# osh_fab_tolerance_test.net
KiCad netlist of a schematic drawn in EAGLE
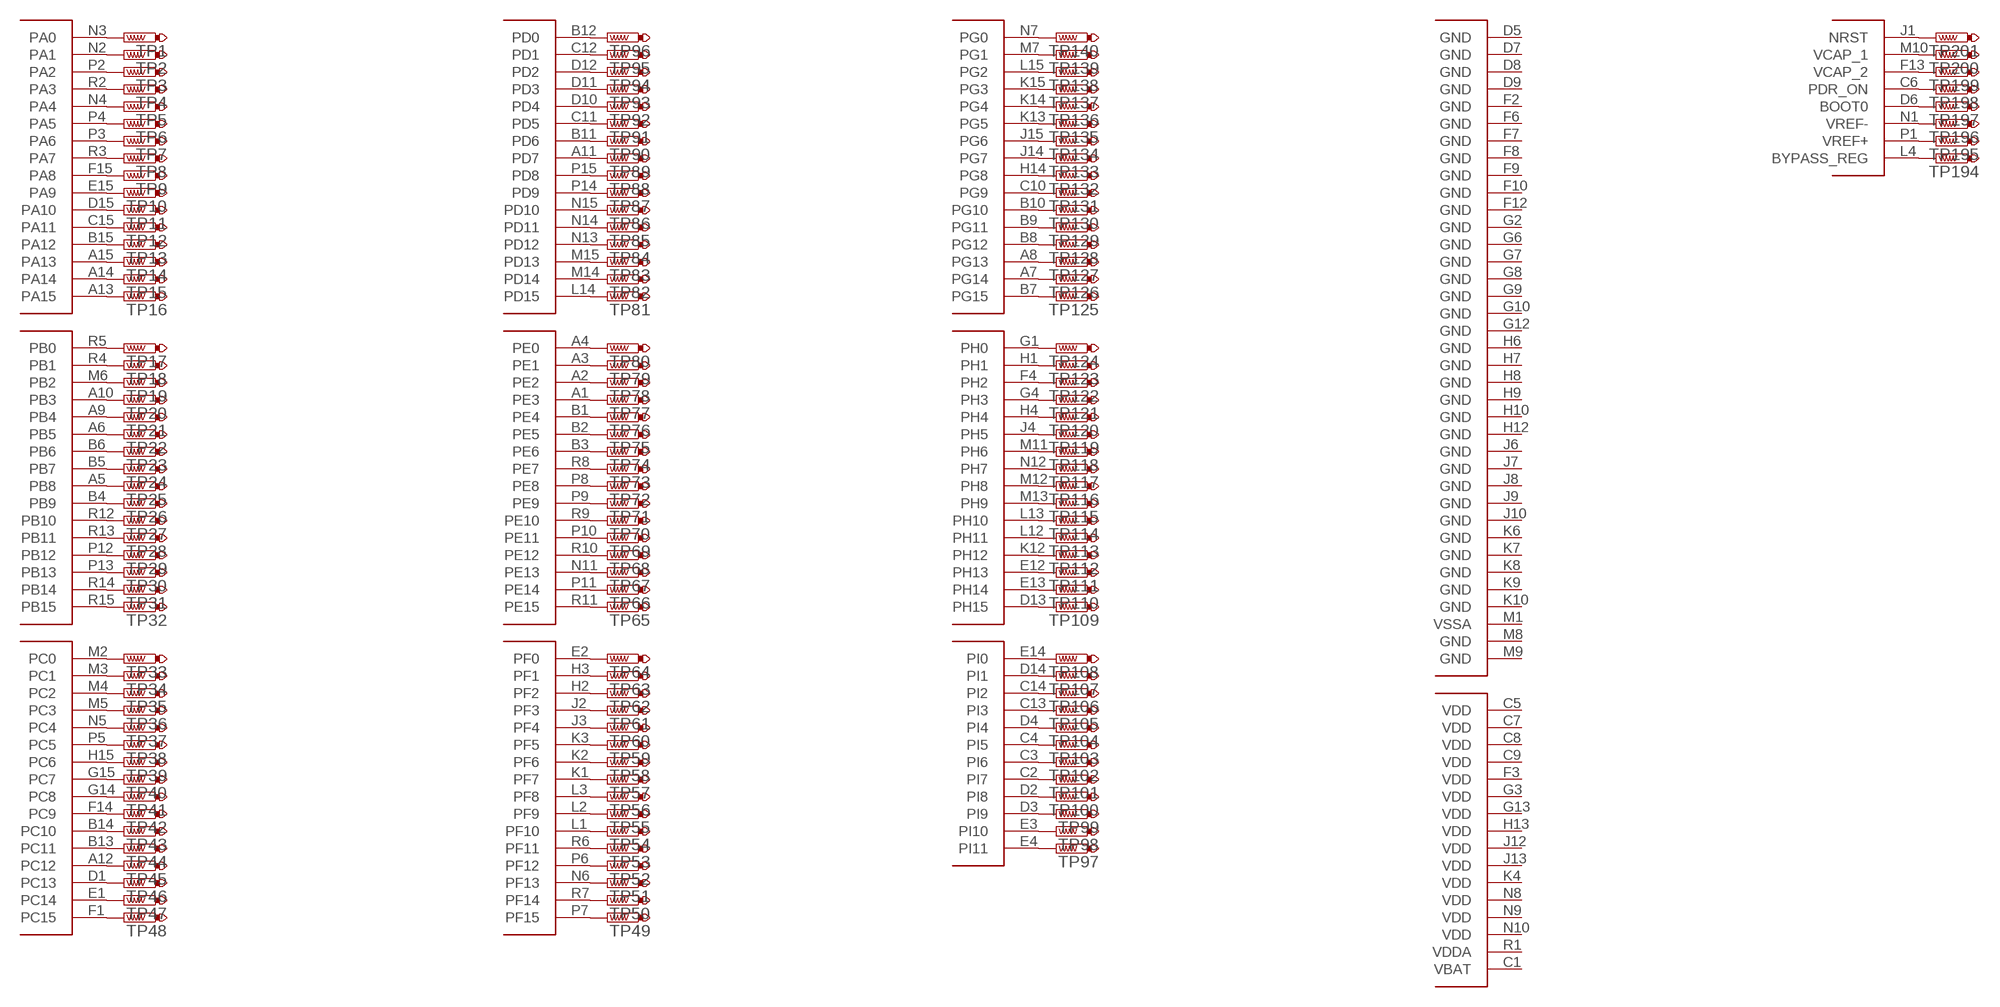
[diagram p0: schematic, sheet 1]

(export (version "E")
  (design (tool "Eeschema 10.0.6"))
  (components
    (comp (ref "TP1")
      (value "PTR1TP09R")
      (footprint "eagle-import:TP09R")
      (libsource (lib "eagle-import") (part "PTR1TP09R"))
    )
    (comp (ref "TP2")
      (value "PTR1TP09R")
      (footprint "eagle-import:TP09R")
      (libsource (lib "eagle-import") (part "PTR1TP09R"))
    )
    (comp (ref "TP3")
      (value "PTR1TP09R")
      (footprint "eagle-import:TP09R")
      (libsource (lib "eagle-import") (part "PTR1TP09R"))
    )
    (comp (ref "TP4")
      (value "PTR1TP09R")
      (footprint "eagle-import:TP09R")
      (libsource (lib "eagle-import") (part "PTR1TP09R"))
    )
    (comp (ref "TP5")
      (value "PTR1TP09R")
      (footprint "eagle-import:TP09R")
      (libsource (lib "eagle-import") (part "PTR1TP09R"))
    )
    (comp (ref "TP6")
      (value "PTR1TP09R")
      (footprint "eagle-import:TP09R")
      (libsource (lib "eagle-import") (part "PTR1TP09R"))
    )
    (comp (ref "TP7")
      (value "PTR1TP09R")
      (footprint "eagle-import:TP09R")
      (libsource (lib "eagle-import") (part "PTR1TP09R"))
    )
    (comp (ref "TP8")
      (value "PTR1TP09R")
      (footprint "eagle-import:TP09R")
      (libsource (lib "eagle-import") (part "PTR1TP09R"))
    )
    (comp (ref "TP9")
      (value "PTR1TP09R")
      (footprint "eagle-import:TP09R")
      (libsource (lib "eagle-import") (part "PTR1TP09R"))
    )
    (comp (ref "TP10")
      (value "PTR1TP09R")
      (footprint "eagle-import:TP09R")
      (libsource (lib "eagle-import") (part "PTR1TP09R"))
    )
    (comp (ref "TP11")
      (value "PTR1TP09R")
      (footprint "eagle-import:TP09R")
      (libsource (lib "eagle-import") (part "PTR1TP09R"))
    )
    (comp (ref "TP12")
      (value "PTR1TP09R")
      (footprint "eagle-import:TP09R")
      (libsource (lib "eagle-import") (part "PTR1TP09R"))
    )
    (comp (ref "TP13")
      (value "PTR1TP09R")
      (footprint "eagle-import:TP09R")
      (libsource (lib "eagle-import") (part "PTR1TP09R"))
    )
    (comp (ref "TP14")
      (value "PTR1TP09R")
      (footprint "eagle-import:TP09R")
      (libsource (lib "eagle-import") (part "PTR1TP09R"))
    )
    (comp (ref "TP15")
      (value "PTR1TP09R")
      (footprint "eagle-import:TP09R")
      (libsource (lib "eagle-import") (part "PTR1TP09R"))
    )
    (comp (ref "TP16")
      (value "PTR1TP09R")
      (footprint "eagle-import:TP09R")
      (libsource (lib "eagle-import") (part "PTR1TP09R"))
    )
    (comp (ref "TP17")
      (value "PTR1TP09R")
      (footprint "eagle-import:TP09R")
      (libsource (lib "eagle-import") (part "PTR1TP09R"))
    )
    (comp (ref "TP18")
      (value "PTR1TP09R")
      (footprint "eagle-import:TP09R")
      (libsource (lib "eagle-import") (part "PTR1TP09R"))
    )
    (comp (ref "TP19")
      (value "PTR1TP09R")
      (footprint "eagle-import:TP09R")
      (libsource (lib "eagle-import") (part "PTR1TP09R"))
    )
    (comp (ref "TP20")
      (value "PTR1TP09R")
      (footprint "eagle-import:TP09R")
      (libsource (lib "eagle-import") (part "PTR1TP09R"))
    )
    (comp (ref "TP21")
      (value "PTR1TP09R")
      (footprint "eagle-import:TP09R")
      (libsource (lib "eagle-import") (part "PTR1TP09R"))
    )
    (comp (ref "TP22")
      (value "PTR1TP09R")
      (footprint "eagle-import:TP09R")
      (libsource (lib "eagle-import") (part "PTR1TP09R"))
    )
    (comp (ref "TP23")
      (value "PTR1TP09R")
      (footprint "eagle-import:TP09R")
      (libsource (lib "eagle-import") (part "PTR1TP09R"))
    )
    (comp (ref "TP24")
      (value "PTR1TP09R")
      (footprint "eagle-import:TP09R")
      (libsource (lib "eagle-import") (part "PTR1TP09R"))
    )
    (comp (ref "TP25")
      (value "PTR1TP09R")
      (footprint "eagle-import:TP09R")
      (libsource (lib "eagle-import") (part "PTR1TP09R"))
    )
    (comp (ref "TP26")
      (value "PTR1TP09R")
      (footprint "eagle-import:TP09R")
      (libsource (lib "eagle-import") (part "PTR1TP09R"))
    )
    (comp (ref "TP27")
      (value "PTR1TP09R")
      (footprint "eagle-import:TP09R")
      (libsource (lib "eagle-import") (part "PTR1TP09R"))
    )
    (comp (ref "TP28")
      (value "PTR1TP09R")
      (footprint "eagle-import:TP09R")
      (libsource (lib "eagle-import") (part "PTR1TP09R"))
    )
    (comp (ref "TP29")
      (value "PTR1TP09R")
      (footprint "eagle-import:TP09R")
      (libsource (lib "eagle-import") (part "PTR1TP09R"))
    )
    (comp (ref "TP30")
      (value "PTR1TP09R")
      (footprint "eagle-import:TP09R")
      (libsource (lib "eagle-import") (part "PTR1TP09R"))
    )
    (comp (ref "TP31")
      (value "PTR1TP09R")
      (footprint "eagle-import:TP09R")
      (libsource (lib "eagle-import") (part "PTR1TP09R"))
    )
    (comp (ref "TP32")
      (value "PTR1TP09R")
      (footprint "eagle-import:TP09R")
      (libsource (lib "eagle-import") (part "PTR1TP09R"))
    )
    (comp (ref "TP33")
      (value "PTR1TP09R")
      (footprint "eagle-import:TP09R")
      (libsource (lib "eagle-import") (part "PTR1TP09R"))
    )
    (comp (ref "TP34")
      (value "PTR1TP09R")
      (footprint "eagle-import:TP09R")
      (libsource (lib "eagle-import") (part "PTR1TP09R"))
    )
    (comp (ref "TP35")
      (value "PTR1TP09R")
      (footprint "eagle-import:TP09R")
      (libsource (lib "eagle-import") (part "PTR1TP09R"))
    )
    (comp (ref "TP36")
      (value "PTR1TP09R")
      (footprint "eagle-import:TP09R")
      (libsource (lib "eagle-import") (part "PTR1TP09R"))
    )
    (comp (ref "TP37")
      (value "PTR1TP09R")
      (footprint "eagle-import:TP09R")
      (libsource (lib "eagle-import") (part "PTR1TP09R"))
    )
    (comp (ref "TP38")
      (value "PTR1TP09R")
      (footprint "eagle-import:TP09R")
      (libsource (lib "eagle-import") (part "PTR1TP09R"))
    )
    (comp (ref "TP39")
      (value "PTR1TP09R")
      (footprint "eagle-import:TP09R")
      (libsource (lib "eagle-import") (part "PTR1TP09R"))
    )
    (comp (ref "TP40")
      (value "PTR1TP09R")
      (footprint "eagle-import:TP09R")
      (libsource (lib "eagle-import") (part "PTR1TP09R"))
    )
    (comp (ref "TP41")
      (value "PTR1TP09R")
      (footprint "eagle-import:TP09R")
      (libsource (lib "eagle-import") (part "PTR1TP09R"))
    )
    (comp (ref "TP42")
      (value "PTR1TP09R")
      (footprint "eagle-import:TP09R")
      (libsource (lib "eagle-import") (part "PTR1TP09R"))
    )
    (comp (ref "TP43")
      (value "PTR1TP09R")
      (footprint "eagle-import:TP09R")
      (libsource (lib "eagle-import") (part "PTR1TP09R"))
    )
    (comp (ref "TP44")
      (value "PTR1TP09R")
      (footprint "eagle-import:TP09R")
      (libsource (lib "eagle-import") (part "PTR1TP09R"))
    )
    (comp (ref "TP45")
      (value "PTR1TP09R")
      (footprint "eagle-import:TP09R")
      (libsource (lib "eagle-import") (part "PTR1TP09R"))
    )
    (comp (ref "TP46")
      (value "PTR1TP09R")
      (footprint "eagle-import:TP09R")
      (libsource (lib "eagle-import") (part "PTR1TP09R"))
    )
    (comp (ref "TP47")
      (value "PTR1TP09R")
      (footprint "eagle-import:TP09R")
      (libsource (lib "eagle-import") (part "PTR1TP09R"))
    )
    (comp (ref "TP48")
      (value "PTR1TP09R")
      (footprint "eagle-import:TP09R")
      (libsource (lib "eagle-import") (part "PTR1TP09R"))
    )
    (comp (ref "TP49")
      (value "PTR1TP09R")
      (footprint "eagle-import:TP09R")
      (libsource (lib "eagle-import") (part "PTR1TP09R"))
    )
    (comp (ref "TP50")
      (value "PTR1TP09R")
      (footprint "eagle-import:TP09R")
      (libsource (lib "eagle-import") (part "PTR1TP09R"))
    )
    (comp (ref "TP51")
      (value "PTR1TP09R")
      (footprint "eagle-import:TP09R")
      (libsource (lib "eagle-import") (part "PTR1TP09R"))
    )
    (comp (ref "TP52")
      (value "PTR1TP09R")
      (footprint "eagle-import:TP09R")
      (libsource (lib "eagle-import") (part "PTR1TP09R"))
    )
    (comp (ref "TP53")
      (value "PTR1TP09R")
      (footprint "eagle-import:TP09R")
      (libsource (lib "eagle-import") (part "PTR1TP09R"))
    )
    (comp (ref "TP54")
      (value "PTR1TP09R")
      (footprint "eagle-import:TP09R")
      (libsource (lib "eagle-import") (part "PTR1TP09R"))
    )
    (comp (ref "TP55")
      (value "PTR1TP09R")
      (footprint "eagle-import:TP09R")
      (libsource (lib "eagle-import") (part "PTR1TP09R"))
    )
    (comp (ref "TP56")
      (value "PTR1TP09R")
      (footprint "eagle-import:TP09R")
      (libsource (lib "eagle-import") (part "PTR1TP09R"))
    )
    (comp (ref "TP57")
      (value "PTR1TP09R")
      (footprint "eagle-import:TP09R")
      (libsource (lib "eagle-import") (part "PTR1TP09R"))
    )
    (comp (ref "TP58")
      (value "PTR1TP09R")
      (footprint "eagle-import:TP09R")
      (libsource (lib "eagle-import") (part "PTR1TP09R"))
    )
    (comp (ref "TP59")
      (value "PTR1TP09R")
      (footprint "eagle-import:TP09R")
      (libsource (lib "eagle-import") (part "PTR1TP09R"))
    )
    (comp (ref "TP60")
      (value "PTR1TP09R")
      (footprint "eagle-import:TP09R")
      (libsource (lib "eagle-import") (part "PTR1TP09R"))
    )
    (comp (ref "TP61")
      (value "PTR1TP09R")
      (footprint "eagle-import:TP09R")
      (libsource (lib "eagle-import") (part "PTR1TP09R"))
    )
    (comp (ref "TP62")
      (value "PTR1TP09R")
      (footprint "eagle-import:TP09R")
      (libsource (lib "eagle-import") (part "PTR1TP09R"))
    )
    (comp (ref "TP63")
      (value "PTR1TP09R")
      (footprint "eagle-import:TP09R")
      (libsource (lib "eagle-import") (part "PTR1TP09R"))
    )
    (comp (ref "TP64")
      (value "PTR1TP09R")
      (footprint "eagle-import:TP09R")
      (libsource (lib "eagle-import") (part "PTR1TP09R"))
    )
    (comp (ref "TP65")
      (value "PTR1TP09R")
      (footprint "eagle-import:TP09R")
      (libsource (lib "eagle-import") (part "PTR1TP09R"))
    )
    (comp (ref "TP66")
      (value "PTR1TP09R")
      (footprint "eagle-import:TP09R")
      (libsource (lib "eagle-import") (part "PTR1TP09R"))
    )
    (comp (ref "TP67")
      (value "PTR1TP09R")
      (footprint "eagle-import:TP09R")
      (libsource (lib "eagle-import") (part "PTR1TP09R"))
    )
    (comp (ref "TP68")
      (value "PTR1TP09R")
      (footprint "eagle-import:TP09R")
      (libsource (lib "eagle-import") (part "PTR1TP09R"))
    )
    (comp (ref "TP69")
      (value "PTR1TP09R")
      (footprint "eagle-import:TP09R")
      (libsource (lib "eagle-import") (part "PTR1TP09R"))
    )
    (comp (ref "TP70")
      (value "PTR1TP09R")
      (footprint "eagle-import:TP09R")
      (libsource (lib "eagle-import") (part "PTR1TP09R"))
    )
    (comp (ref "TP71")
      (value "PTR1TP09R")
      (footprint "eagle-import:TP09R")
      (libsource (lib "eagle-import") (part "PTR1TP09R"))
    )
    (comp (ref "TP72")
      (value "PTR1TP09R")
      (footprint "eagle-import:TP09R")
      (libsource (lib "eagle-import") (part "PTR1TP09R"))
    )
    (comp (ref "TP73")
      (value "PTR1TP09R")
      (footprint "eagle-import:TP09R")
      (libsource (lib "eagle-import") (part "PTR1TP09R"))
    )
    (comp (ref "TP74")
      (value "PTR1TP09R")
      (footprint "eagle-import:TP09R")
      (libsource (lib "eagle-import") (part "PTR1TP09R"))
    )
    (comp (ref "TP75")
      (value "PTR1TP09R")
      (footprint "eagle-import:TP09R")
      (libsource (lib "eagle-import") (part "PTR1TP09R"))
    )
    (comp (ref "TP76")
      (value "PTR1TP09R")
      (footprint "eagle-import:TP09R")
      (libsource (lib "eagle-import") (part "PTR1TP09R"))
    )
    (comp (ref "TP77")
      (value "PTR1TP09R")
      (footprint "eagle-import:TP09R")
      (libsource (lib "eagle-import") (part "PTR1TP09R"))
    )
    (comp (ref "TP78")
      (value "PTR1TP09R")
      (footprint "eagle-import:TP09R")
      (libsource (lib "eagle-import") (part "PTR1TP09R"))
    )
    (comp (ref "TP79")
      (value "PTR1TP09R")
      (footprint "eagle-import:TP09R")
      (libsource (lib "eagle-import") (part "PTR1TP09R"))
    )
    (comp (ref "TP80")
      (value "PTR1TP09R")
      (footprint "eagle-import:TP09R")
      (libsource (lib "eagle-import") (part "PTR1TP09R"))
    )
    (comp (ref "TP81")
      (value "PTR1TP09R")
      (footprint "eagle-import:TP09R")
      (libsource (lib "eagle-import") (part "PTR1TP09R"))
    )
    (comp (ref "TP82")
      (value "PTR1TP09R")
      (footprint "eagle-import:TP09R")
      (libsource (lib "eagle-import") (part "PTR1TP09R"))
    )
    (comp (ref "TP83")
      (value "PTR1TP09R")
      (footprint "eagle-import:TP09R")
      (libsource (lib "eagle-import") (part "PTR1TP09R"))
    )
    (comp (ref "TP84")
      (value "PTR1TP09R")
      (footprint "eagle-import:TP09R")
      (libsource (lib "eagle-import") (part "PTR1TP09R"))
    )
    (comp (ref "TP85")
      (value "PTR1TP09R")
      (footprint "eagle-import:TP09R")
      (libsource (lib "eagle-import") (part "PTR1TP09R"))
    )
    (comp (ref "TP86")
      (value "PTR1TP09R")
      (footprint "eagle-import:TP09R")
      (libsource (lib "eagle-import") (part "PTR1TP09R"))
    )
    (comp (ref "TP87")
      (value "PTR1TP09R")
      (footprint "eagle-import:TP09R")
      (libsource (lib "eagle-import") (part "PTR1TP09R"))
    )
    (comp (ref "TP88")
      (value "PTR1TP09R")
      (footprint "eagle-import:TP09R")
      (libsource (lib "eagle-import") (part "PTR1TP09R"))
    )
    (comp (ref "TP89")
      (value "PTR1TP09R")
      (footprint "eagle-import:TP09R")
      (libsource (lib "eagle-import") (part "PTR1TP09R"))
    )
    (comp (ref "TP90")
      (value "PTR1TP09R")
      (footprint "eagle-import:TP09R")
      (libsource (lib "eagle-import") (part "PTR1TP09R"))
    )
    (comp (ref "TP91")
      (value "PTR1TP09R")
      (footprint "eagle-import:TP09R")
      (libsource (lib "eagle-import") (part "PTR1TP09R"))
    )
    (comp (ref "TP92")
      (value "PTR1TP09R")
      (footprint "eagle-import:TP09R")
      (libsource (lib "eagle-import") (part "PTR1TP09R"))
    )
    (comp (ref "TP93")
      (value "PTR1TP09R")
      (footprint "eagle-import:TP09R")
      (libsource (lib "eagle-import") (part "PTR1TP09R"))
    )
    (comp (ref "TP94")
      (value "PTR1TP09R")
      (footprint "eagle-import:TP09R")
      (libsource (lib "eagle-import") (part "PTR1TP09R"))
    )
    (comp (ref "TP95")
      (value "PTR1TP09R")
      (footprint "eagle-import:TP09R")
      (libsource (lib "eagle-import") (part "PTR1TP09R"))
    )
    (comp (ref "TP96")
      (value "PTR1TP09R")
      (footprint "eagle-import:TP09R")
      (libsource (lib "eagle-import") (part "PTR1TP09R"))
    )
    (comp (ref "TP97")
      (value "PTR1TP09R")
      (footprint "eagle-import:TP09R")
      (libsource (lib "eagle-import") (part "PTR1TP09R"))
    )
    (comp (ref "TP98")
      (value "PTR1TP09R")
      (footprint "eagle-import:TP09R")
      (libsource (lib "eagle-import") (part "PTR1TP09R"))
    )
    (comp (ref "TP99")
      (value "PTR1TP09R")
      (footprint "eagle-import:TP09R")
      (libsource (lib "eagle-import") (part "PTR1TP09R"))
    )
    (comp (ref "TP100")
      (value "PTR1TP09R")
      (footprint "eagle-import:TP09R")
      (libsource (lib "eagle-import") (part "PTR1TP09R"))
    )
    (comp (ref "TP101")
      (value "PTR1TP09R")
      (footprint "eagle-import:TP09R")
      (libsource (lib "eagle-import") (part "PTR1TP09R"))
    )
    (comp (ref "TP102")
      (value "PTR1TP09R")
      (footprint "eagle-import:TP09R")
      (libsource (lib "eagle-import") (part "PTR1TP09R"))
    )
    (comp (ref "TP103")
      (value "PTR1TP09R")
      (footprint "eagle-import:TP09R")
      (libsource (lib "eagle-import") (part "PTR1TP09R"))
    )
    (comp (ref "TP104")
      (value "PTR1TP09R")
      (footprint "eagle-import:TP09R")
      (libsource (lib "eagle-import") (part "PTR1TP09R"))
    )
    (comp (ref "TP105")
      (value "PTR1TP09R")
      (footprint "eagle-import:TP09R")
      (libsource (lib "eagle-import") (part "PTR1TP09R"))
    )
    (comp (ref "TP106")
      (value "PTR1TP09R")
      (footprint "eagle-import:TP09R")
      (libsource (lib "eagle-import") (part "PTR1TP09R"))
    )
    (comp (ref "TP107")
      (value "PTR1TP09R")
      (footprint "eagle-import:TP09R")
      (libsource (lib "eagle-import") (part "PTR1TP09R"))
    )
    (comp (ref "TP108")
      (value "PTR1TP09R")
      (footprint "eagle-import:TP09R")
      (libsource (lib "eagle-import") (part "PTR1TP09R"))
    )
    (comp (ref "TP109")
      (value "PTR1TP09R")
      (footprint "eagle-import:TP09R")
      (libsource (lib "eagle-import") (part "PTR1TP09R"))
    )
    (comp (ref "TP110")
      (value "PTR1TP09R")
      (footprint "eagle-import:TP09R")
      (libsource (lib "eagle-import") (part "PTR1TP09R"))
    )
    (comp (ref "TP111")
      (value "PTR1TP09R")
      (footprint "eagle-import:TP09R")
      (libsource (lib "eagle-import") (part "PTR1TP09R"))
    )
    (comp (ref "TP112")
      (value "PTR1TP09R")
      (footprint "eagle-import:TP09R")
      (libsource (lib "eagle-import") (part "PTR1TP09R"))
    )
    (comp (ref "TP113")
      (value "PTR1TP09R")
      (footprint "eagle-import:TP09R")
      (libsource (lib "eagle-import") (part "PTR1TP09R"))
    )
    (comp (ref "TP114")
      (value "PTR1TP09R")
      (footprint "eagle-import:TP09R")
      (libsource (lib "eagle-import") (part "PTR1TP09R"))
    )
    (comp (ref "TP115")
      (value "PTR1TP09R")
      (footprint "eagle-import:TP09R")
      (libsource (lib "eagle-import") (part "PTR1TP09R"))
    )
    (comp (ref "TP116")
      (value "PTR1TP09R")
      (footprint "eagle-import:TP09R")
      (libsource (lib "eagle-import") (part "PTR1TP09R"))
    )
    (comp (ref "TP117")
      (value "PTR1TP09R")
      (footprint "eagle-import:TP09R")
      (libsource (lib "eagle-import") (part "PTR1TP09R"))
    )
    (comp (ref "TP118")
      (value "PTR1TP09R")
      (footprint "eagle-import:TP09R")
      (libsource (lib "eagle-import") (part "PTR1TP09R"))
    )
    (comp (ref "TP119")
      (value "PTR1TP09R")
      (footprint "eagle-import:TP09R")
      (libsource (lib "eagle-import") (part "PTR1TP09R"))
    )
    (comp (ref "TP120")
      (value "PTR1TP09R")
      (footprint "eagle-import:TP09R")
      (libsource (lib "eagle-import") (part "PTR1TP09R"))
    )
    (comp (ref "TP121")
      (value "PTR1TP09R")
      (footprint "eagle-import:TP09R")
      (libsource (lib "eagle-import") (part "PTR1TP09R"))
    )
    (comp (ref "TP122")
      (value "PTR1TP09R")
      (footprint "eagle-import:TP09R")
      (libsource (lib "eagle-import") (part "PTR1TP09R"))
    )
    (comp (ref "TP123")
      (value "PTR1TP09R")
      (footprint "eagle-import:TP09R")
      (libsource (lib "eagle-import") (part "PTR1TP09R"))
    )
    (comp (ref "TP124")
      (value "PTR1TP09R")
      (footprint "eagle-import:TP09R")
      (libsource (lib "eagle-import") (part "PTR1TP09R"))
    )
    (comp (ref "TP125")
      (value "PTR1TP09R")
      (footprint "eagle-import:TP09R")
      (libsource (lib "eagle-import") (part "PTR1TP09R"))
    )
    (comp (ref "TP126")
      (value "PTR1TP09R")
      (footprint "eagle-import:TP09R")
      (libsource (lib "eagle-import") (part "PTR1TP09R"))
    )
    (comp (ref "TP127")
      (value "PTR1TP09R")
      (footprint "eagle-import:TP09R")
      (libsource (lib "eagle-import") (part "PTR1TP09R"))
    )
    (comp (ref "TP128")
      (value "PTR1TP09R")
      (footprint "eagle-import:TP09R")
      (libsource (lib "eagle-import") (part "PTR1TP09R"))
    )
    (comp (ref "TP129")
      (value "PTR1TP09R")
      (footprint "eagle-import:TP09R")
      (libsource (lib "eagle-import") (part "PTR1TP09R"))
    )
    (comp (ref "TP130")
      (value "PTR1TP09R")
      (footprint "eagle-import:TP09R")
      (libsource (lib "eagle-import") (part "PTR1TP09R"))
    )
    (comp (ref "TP131")
      (value "PTR1TP09R")
      (footprint "eagle-import:TP09R")
      (libsource (lib "eagle-import") (part "PTR1TP09R"))
    )
    (comp (ref "TP132")
      (value "PTR1TP09R")
      (footprint "eagle-import:TP09R")
      (libsource (lib "eagle-import") (part "PTR1TP09R"))
    )
    (comp (ref "TP133")
      (value "PTR1TP09R")
      (footprint "eagle-import:TP09R")
      (libsource (lib "eagle-import") (part "PTR1TP09R"))
    )
    (comp (ref "TP134")
      (value "PTR1TP09R")
      (footprint "eagle-import:TP09R")
      (libsource (lib "eagle-import") (part "PTR1TP09R"))
    )
    (comp (ref "TP135")
      (value "PTR1TP09R")
      (footprint "eagle-import:TP09R")
      (libsource (lib "eagle-import") (part "PTR1TP09R"))
    )
    (comp (ref "TP136")
      (value "PTR1TP09R")
      (footprint "eagle-import:TP09R")
      (libsource (lib "eagle-import") (part "PTR1TP09R"))
    )
    (comp (ref "TP137")
      (value "PTR1TP09R")
      (footprint "eagle-import:TP09R")
      (libsource (lib "eagle-import") (part "PTR1TP09R"))
    )
    (comp (ref "TP138")
      (value "PTR1TP09R")
      (footprint "eagle-import:TP09R")
      (libsource (lib "eagle-import") (part "PTR1TP09R"))
    )
    (comp (ref "TP139")
      (value "PTR1TP09R")
      (footprint "eagle-import:TP09R")
      (libsource (lib "eagle-import") (part "PTR1TP09R"))
    )
    (comp (ref "TP140")
      (value "PTR1TP09R")
      (footprint "eagle-import:TP09R")
      (libsource (lib "eagle-import") (part "PTR1TP09R"))
    )
    (comp (ref "TP194")
      (value "PTR1TP09R")
      (footprint "eagle-import:TP09R")
      (libsource (lib "eagle-import") (part "PTR1TP09R"))
    )
    (comp (ref "TP195")
      (value "PTR1TP09R")
      (footprint "eagle-import:TP09R")
      (libsource (lib "eagle-import") (part "PTR1TP09R"))
    )
    (comp (ref "TP196")
      (value "PTR1TP09R")
      (footprint "eagle-import:TP09R")
      (libsource (lib "eagle-import") (part "PTR1TP09R"))
    )
    (comp (ref "TP197")
      (value "PTR1TP09R")
      (footprint "eagle-import:TP09R")
      (libsource (lib "eagle-import") (part "PTR1TP09R"))
    )
    (comp (ref "TP198")
      (value "PTR1TP09R")
      (footprint "eagle-import:TP09R")
      (libsource (lib "eagle-import") (part "PTR1TP09R"))
    )
    (comp (ref "TP199")
      (value "PTR1TP09R")
      (footprint "eagle-import:TP09R")
      (libsource (lib "eagle-import") (part "PTR1TP09R"))
    )
    (comp (ref "TP200")
      (value "PTR1TP09R")
      (footprint "eagle-import:TP09R")
      (libsource (lib "eagle-import") (part "PTR1TP09R"))
    )
    (comp (ref "TP201")
      (value "PTR1TP09R")
      (footprint "eagle-import:TP09R")
      (libsource (lib "eagle-import") (part "PTR1TP09R"))
    )
    (comp (ref "U$1")
      (value "STM32_32BIT_MCU_STM32F407IG")
      (footprint "eagle-import:STM32_32BIT_MCU_UFBGA176+25")
      (libsource (lib "eagle-import") (part "STM32_32BIT_MCU_STM32F407IG"))
    )
  )
  (nets
    (net (code "1") (name "Net-(U$1-BOOT0)") (class "Default")
      (node (ref "TP197") (pin "TP") (pinfunction "TP_TP") (pintype "input"))
      (node (ref "U$1") (pin "D6") (pinfunction "BOOT0_D6") (pintype "bidirectional"))
    )
    (net (code "2") (name "Net-(U$1-BYPASS_REG)") (class "Default")
      (node (ref "TP194") (pin "TP") (pinfunction "TP_TP") (pintype "input"))
      (node (ref "U$1") (pin "L4") (pinfunction "BYPASS_REG_L4") (pintype "bidirectional"))
    )
    (net (code "3") (name "Net-(U$1-NRST)") (class "Default")
      (node (ref "TP201") (pin "TP") (pinfunction "TP_TP") (pintype "input"))
      (node (ref "U$1") (pin "J1") (pinfunction "NRST_J1") (pintype "bidirectional"))
    )
    (net (code "4") (name "Net-(U$1-PA0)") (class "Default")
      (node (ref "TP1") (pin "TP") (pinfunction "TP_TP") (pintype "input"))
      (node (ref "U$1") (pin "N3") (pinfunction "PA0_N3") (pintype "bidirectional"))
    )
    (net (code "5") (name "Net-(U$1-PA1)") (class "Default")
      (node (ref "TP2") (pin "TP") (pinfunction "TP_TP") (pintype "input"))
      (node (ref "U$1") (pin "N2") (pinfunction "PA1_N2") (pintype "bidirectional"))
    )
    (net (code "6") (name "Net-(U$1-PA2)") (class "Default")
      (node (ref "TP3") (pin "TP") (pinfunction "TP_TP") (pintype "input"))
      (node (ref "U$1") (pin "P2") (pinfunction "PA2_P2") (pintype "bidirectional"))
    )
    (net (code "7") (name "Net-(U$1-PA3)") (class "Default")
      (node (ref "TP4") (pin "TP") (pinfunction "TP_TP") (pintype "input"))
      (node (ref "U$1") (pin "R2") (pinfunction "PA3_R2") (pintype "bidirectional"))
    )
    (net (code "8") (name "Net-(U$1-PA4)") (class "Default")
      (node (ref "TP5") (pin "TP") (pinfunction "TP_TP") (pintype "input"))
      (node (ref "U$1") (pin "N4") (pinfunction "PA4_N4") (pintype "bidirectional"))
    )
    (net (code "9") (name "Net-(U$1-PA5)") (class "Default")
      (node (ref "TP6") (pin "TP") (pinfunction "TP_TP") (pintype "input"))
      (node (ref "U$1") (pin "P4") (pinfunction "PA5_P4") (pintype "bidirectional"))
    )
    (net (code "10") (name "Net-(U$1-PA6)") (class "Default")
      (node (ref "TP7") (pin "TP") (pinfunction "TP_TP") (pintype "input"))
      (node (ref "U$1") (pin "P3") (pinfunction "PA6_P3") (pintype "bidirectional"))
    )
    (net (code "11") (name "Net-(U$1-PA7)") (class "Default")
      (node (ref "TP8") (pin "TP") (pinfunction "TP_TP") (pintype "input"))
      (node (ref "U$1") (pin "R3") (pinfunction "PA7_R3") (pintype "bidirectional"))
    )
    (net (code "12") (name "Net-(U$1-PA8)") (class "Default")
      (node (ref "TP9") (pin "TP") (pinfunction "TP_TP") (pintype "input"))
      (node (ref "U$1") (pin "F15") (pinfunction "PA8_F15") (pintype "bidirectional"))
    )
    (net (code "13") (name "Net-(U$1-PA9)") (class "Default")
      (node (ref "TP10") (pin "TP") (pinfunction "TP_TP") (pintype "input"))
      (node (ref "U$1") (pin "E15") (pinfunction "PA9_E15") (pintype "bidirectional"))
    )
    (net (code "14") (name "Net-(U$1-PA10)") (class "Default")
      (node (ref "TP11") (pin "TP") (pinfunction "TP_TP") (pintype "input"))
      (node (ref "U$1") (pin "D15") (pinfunction "PA10_D15") (pintype "bidirectional"))
    )
    (net (code "15") (name "Net-(U$1-PA11)") (class "Default")
      (node (ref "TP12") (pin "TP") (pinfunction "TP_TP") (pintype "input"))
      (node (ref "U$1") (pin "C15") (pinfunction "PA11_C15") (pintype "bidirectional"))
    )
    (net (code "16") (name "Net-(U$1-PA12)") (class "Default")
      (node (ref "TP13") (pin "TP") (pinfunction "TP_TP") (pintype "input"))
      (node (ref "U$1") (pin "B15") (pinfunction "PA12_B15") (pintype "bidirectional"))
    )
    (net (code "17") (name "Net-(U$1-PA13)") (class "Default")
      (node (ref "TP14") (pin "TP") (pinfunction "TP_TP") (pintype "input"))
      (node (ref "U$1") (pin "A15") (pinfunction "PA13_A15") (pintype "bidirectional"))
    )
    (net (code "18") (name "Net-(U$1-PA14)") (class "Default")
      (node (ref "TP15") (pin "TP") (pinfunction "TP_TP") (pintype "input"))
      (node (ref "U$1") (pin "A14") (pinfunction "PA14_A14") (pintype "bidirectional"))
    )
    (net (code "19") (name "Net-(U$1-PA15)") (class "Default")
      (node (ref "TP16") (pin "TP") (pinfunction "TP_TP") (pintype "input"))
      (node (ref "U$1") (pin "A13") (pinfunction "PA15_A13") (pintype "bidirectional"))
    )
    (net (code "20") (name "Net-(U$1-PB0)") (class "Default")
      (node (ref "TP17") (pin "TP") (pinfunction "TP_TP") (pintype "input"))
      (node (ref "U$1") (pin "R5") (pinfunction "PB0_R5") (pintype "bidirectional"))
    )
    (net (code "21") (name "Net-(U$1-PB1)") (class "Default")
      (node (ref "TP18") (pin "TP") (pinfunction "TP_TP") (pintype "input"))
      (node (ref "U$1") (pin "R4") (pinfunction "PB1_R4") (pintype "bidirectional"))
    )
    (net (code "22") (name "Net-(U$1-PB2)") (class "Default")
      (node (ref "TP19") (pin "TP") (pinfunction "TP_TP") (pintype "input"))
      (node (ref "U$1") (pin "M6") (pinfunction "PB2_M6") (pintype "bidirectional"))
    )
    (net (code "23") (name "Net-(U$1-PB3)") (class "Default")
      (node (ref "TP20") (pin "TP") (pinfunction "TP_TP") (pintype "input"))
      (node (ref "U$1") (pin "A10") (pinfunction "PB3_A10") (pintype "bidirectional"))
    )
    (net (code "24") (name "Net-(U$1-PB4)") (class "Default")
      (node (ref "TP21") (pin "TP") (pinfunction "TP_TP") (pintype "input"))
      (node (ref "U$1") (pin "A9") (pinfunction "PB4_A9") (pintype "bidirectional"))
    )
    (net (code "25") (name "Net-(U$1-PB5)") (class "Default")
      (node (ref "TP22") (pin "TP") (pinfunction "TP_TP") (pintype "input"))
      (node (ref "U$1") (pin "A6") (pinfunction "PB5_A6") (pintype "bidirectional"))
    )
    (net (code "26") (name "Net-(U$1-PB6)") (class "Default")
      (node (ref "TP23") (pin "TP") (pinfunction "TP_TP") (pintype "input"))
      (node (ref "U$1") (pin "B6") (pinfunction "PB6_B6") (pintype "bidirectional"))
    )
    (net (code "27") (name "Net-(U$1-PB7)") (class "Default")
      (node (ref "TP24") (pin "TP") (pinfunction "TP_TP") (pintype "input"))
      (node (ref "U$1") (pin "B5") (pinfunction "PB7_B5") (pintype "bidirectional"))
    )
    (net (code "28") (name "Net-(U$1-PB8)") (class "Default")
      (node (ref "TP25") (pin "TP") (pinfunction "TP_TP") (pintype "input"))
      (node (ref "U$1") (pin "A5") (pinfunction "PB8_A5") (pintype "bidirectional"))
    )
    (net (code "29") (name "Net-(U$1-PB9)") (class "Default")
      (node (ref "TP26") (pin "TP") (pinfunction "TP_TP") (pintype "input"))
      (node (ref "U$1") (pin "B4") (pinfunction "PB9_B4") (pintype "bidirectional"))
    )
    (net (code "30") (name "Net-(U$1-PB10)") (class "Default")
      (node (ref "TP27") (pin "TP") (pinfunction "TP_TP") (pintype "input"))
      (node (ref "U$1") (pin "R12") (pinfunction "PB10_R12") (pintype "bidirectional"))
    )
    (net (code "31") (name "Net-(U$1-PB11)") (class "Default")
      (node (ref "TP28") (pin "TP") (pinfunction "TP_TP") (pintype "input"))
      (node (ref "U$1") (pin "R13") (pinfunction "PB11_R13") (pintype "bidirectional"))
    )
    (net (code "32") (name "Net-(U$1-PB12)") (class "Default")
      (node (ref "TP29") (pin "TP") (pinfunction "TP_TP") (pintype "input"))
      (node (ref "U$1") (pin "P12") (pinfunction "PB12_P12") (pintype "bidirectional"))
    )
    (net (code "33") (name "Net-(U$1-PB13)") (class "Default")
      (node (ref "TP30") (pin "TP") (pinfunction "TP_TP") (pintype "input"))
      (node (ref "U$1") (pin "P13") (pinfunction "PB13_P13") (pintype "bidirectional"))
    )
    (net (code "34") (name "Net-(U$1-PB14)") (class "Default")
      (node (ref "TP31") (pin "TP") (pinfunction "TP_TP") (pintype "input"))
      (node (ref "U$1") (pin "R14") (pinfunction "PB14_R14") (pintype "bidirectional"))
    )
    (net (code "35") (name "Net-(U$1-PB15)") (class "Default")
      (node (ref "TP32") (pin "TP") (pinfunction "TP_TP") (pintype "input"))
      (node (ref "U$1") (pin "R15") (pinfunction "PB15_R15") (pintype "bidirectional"))
    )
    (net (code "36") (name "Net-(U$1-PC0)") (class "Default")
      (node (ref "TP33") (pin "TP") (pinfunction "TP_TP") (pintype "input"))
      (node (ref "U$1") (pin "M2") (pinfunction "PC0_M2") (pintype "bidirectional"))
    )
    (net (code "37") (name "Net-(U$1-PC1)") (class "Default")
      (node (ref "TP34") (pin "TP") (pinfunction "TP_TP") (pintype "input"))
      (node (ref "U$1") (pin "M3") (pinfunction "PC1_M3") (pintype "bidirectional"))
    )
    (net (code "38") (name "Net-(U$1-PC2)") (class "Default")
      (node (ref "TP35") (pin "TP") (pinfunction "TP_TP") (pintype "input"))
      (node (ref "U$1") (pin "M4") (pinfunction "PC2_M4") (pintype "bidirectional"))
    )
    (net (code "39") (name "Net-(U$1-PC3)") (class "Default")
      (node (ref "TP36") (pin "TP") (pinfunction "TP_TP") (pintype "input"))
      (node (ref "U$1") (pin "M5") (pinfunction "PC3_M5") (pintype "bidirectional"))
    )
    (net (code "40") (name "Net-(U$1-PC4)") (class "Default")
      (node (ref "TP37") (pin "TP") (pinfunction "TP_TP") (pintype "input"))
      (node (ref "U$1") (pin "N5") (pinfunction "PC4_N5") (pintype "bidirectional"))
    )
    (net (code "41") (name "Net-(U$1-PC5)") (class "Default")
      (node (ref "TP38") (pin "TP") (pinfunction "TP_TP") (pintype "input"))
      (node (ref "U$1") (pin "P5") (pinfunction "PC5_P5") (pintype "bidirectional"))
    )
    (net (code "42") (name "Net-(U$1-PC6)") (class "Default")
      (node (ref "TP39") (pin "TP") (pinfunction "TP_TP") (pintype "input"))
      (node (ref "U$1") (pin "H15") (pinfunction "PC6_H15") (pintype "bidirectional"))
    )
    (net (code "43") (name "Net-(U$1-PC7)") (class "Default")
      (node (ref "TP40") (pin "TP") (pinfunction "TP_TP") (pintype "input"))
      (node (ref "U$1") (pin "G15") (pinfunction "PC7_G15") (pintype "bidirectional"))
    )
    (net (code "44") (name "Net-(U$1-PC8)") (class "Default")
      (node (ref "TP41") (pin "TP") (pinfunction "TP_TP") (pintype "input"))
      (node (ref "U$1") (pin "G14") (pinfunction "PC8_G14") (pintype "bidirectional"))
    )
    (net (code "45") (name "Net-(U$1-PC9)") (class "Default")
      (node (ref "TP42") (pin "TP") (pinfunction "TP_TP") (pintype "input"))
      (node (ref "U$1") (pin "F14") (pinfunction "PC9_F14") (pintype "bidirectional"))
    )
    (net (code "46") (name "Net-(U$1-PC10)") (class "Default")
      (node (ref "TP43") (pin "TP") (pinfunction "TP_TP") (pintype "input"))
      (node (ref "U$1") (pin "B14") (pinfunction "PC10_B14") (pintype "bidirectional"))
    )
    (net (code "47") (name "Net-(U$1-PC11)") (class "Default")
      (node (ref "TP44") (pin "TP") (pinfunction "TP_TP") (pintype "input"))
      (node (ref "U$1") (pin "B13") (pinfunction "PC11_B13") (pintype "bidirectional"))
    )
    (net (code "48") (name "Net-(U$1-PC12)") (class "Default")
      (node (ref "TP45") (pin "TP") (pinfunction "TP_TP") (pintype "input"))
      (node (ref "U$1") (pin "A12") (pinfunction "PC12_A12") (pintype "bidirectional"))
    )
    (net (code "49") (name "Net-(U$1-PC13)") (class "Default")
      (node (ref "TP46") (pin "TP") (pinfunction "TP_TP") (pintype "input"))
      (node (ref "U$1") (pin "D1") (pinfunction "PC13_D1") (pintype "bidirectional"))
    )
    (net (code "50") (name "Net-(U$1-PC14)") (class "Default")
      (node (ref "TP47") (pin "TP") (pinfunction "TP_TP") (pintype "input"))
      (node (ref "U$1") (pin "E1") (pinfunction "PC14_E1") (pintype "bidirectional"))
    )
    (net (code "51") (name "Net-(U$1-PC15)") (class "Default")
      (node (ref "TP48") (pin "TP") (pinfunction "TP_TP") (pintype "input"))
      (node (ref "U$1") (pin "F1") (pinfunction "PC15_F1") (pintype "bidirectional"))
    )
    (net (code "52") (name "Net-(U$1-PD0)") (class "Default")
      (node (ref "TP96") (pin "TP") (pinfunction "TP_TP") (pintype "input"))
      (node (ref "U$1") (pin "B12") (pinfunction "PD0_B12") (pintype "bidirectional"))
    )
    (net (code "53") (name "Net-(U$1-PD1)") (class "Default")
      (node (ref "TP95") (pin "TP") (pinfunction "TP_TP") (pintype "input"))
      (node (ref "U$1") (pin "C12") (pinfunction "PD1_C12") (pintype "bidirectional"))
    )
    (net (code "54") (name "Net-(U$1-PD2)") (class "Default")
      (node (ref "TP94") (pin "TP") (pinfunction "TP_TP") (pintype "input"))
      (node (ref "U$1") (pin "D12") (pinfunction "PD2_D12") (pintype "bidirectional"))
    )
    (net (code "55") (name "Net-(U$1-PD3)") (class "Default")
      (node (ref "TP93") (pin "TP") (pinfunction "TP_TP") (pintype "input"))
      (node (ref "U$1") (pin "D11") (pinfunction "PD3_D11") (pintype "bidirectional"))
    )
    (net (code "56") (name "Net-(U$1-PD4)") (class "Default")
      (node (ref "TP92") (pin "TP") (pinfunction "TP_TP") (pintype "input"))
      (node (ref "U$1") (pin "D10") (pinfunction "PD4_D10") (pintype "bidirectional"))
    )
    (net (code "57") (name "Net-(U$1-PD5)") (class "Default")
      (node (ref "TP91") (pin "TP") (pinfunction "TP_TP") (pintype "input"))
      (node (ref "U$1") (pin "C11") (pinfunction "PD5_C11") (pintype "bidirectional"))
    )
    (net (code "58") (name "Net-(U$1-PD6)") (class "Default")
      (node (ref "TP90") (pin "TP") (pinfunction "TP_TP") (pintype "input"))
      (node (ref "U$1") (pin "B11") (pinfunction "PD6_B11") (pintype "bidirectional"))
    )
    (net (code "59") (name "Net-(U$1-PD7)") (class "Default")
      (node (ref "TP89") (pin "TP") (pinfunction "TP_TP") (pintype "input"))
      (node (ref "U$1") (pin "A11") (pinfunction "PD7_A11") (pintype "bidirectional"))
    )
    (net (code "60") (name "Net-(U$1-PD8)") (class "Default")
      (node (ref "TP88") (pin "TP") (pinfunction "TP_TP") (pintype "input"))
      (node (ref "U$1") (pin "P15") (pinfunction "PD8_P15") (pintype "bidirectional"))
    )
    (net (code "61") (name "Net-(U$1-PD9)") (class "Default")
      (node (ref "TP87") (pin "TP") (pinfunction "TP_TP") (pintype "input"))
      (node (ref "U$1") (pin "P14") (pinfunction "PD9_P14") (pintype "bidirectional"))
    )
    (net (code "62") (name "Net-(U$1-PD10)") (class "Default")
      (node (ref "TP86") (pin "TP") (pinfunction "TP_TP") (pintype "input"))
      (node (ref "U$1") (pin "N15") (pinfunction "PD10_N15") (pintype "bidirectional"))
    )
    (net (code "63") (name "Net-(U$1-PD11)") (class "Default")
      (node (ref "TP85") (pin "TP") (pinfunction "TP_TP") (pintype "input"))
      (node (ref "U$1") (pin "N14") (pinfunction "PD11_N14") (pintype "bidirectional"))
    )
    (net (code "64") (name "Net-(U$1-PD12)") (class "Default")
      (node (ref "TP84") (pin "TP") (pinfunction "TP_TP") (pintype "input"))
      (node (ref "U$1") (pin "N13") (pinfunction "PD12_N13") (pintype "bidirectional"))
    )
    (net (code "65") (name "Net-(U$1-PD13)") (class "Default")
      (node (ref "TP83") (pin "TP") (pinfunction "TP_TP") (pintype "input"))
      (node (ref "U$1") (pin "M15") (pinfunction "PD13_M15") (pintype "bidirectional"))
    )
    (net (code "66") (name "Net-(U$1-PD14)") (class "Default")
      (node (ref "TP82") (pin "TP") (pinfunction "TP_TP") (pintype "input"))
      (node (ref "U$1") (pin "M14") (pinfunction "PD14_M14") (pintype "bidirectional"))
    )
    (net (code "67") (name "Net-(U$1-PD15)") (class "Default")
      (node (ref "TP81") (pin "TP") (pinfunction "TP_TP") (pintype "input"))
      (node (ref "U$1") (pin "L14") (pinfunction "PD15_L14") (pintype "bidirectional"))
    )
    (net (code "68") (name "Net-(U$1-PDR_ON)") (class "Default")
      (node (ref "TP198") (pin "TP") (pinfunction "TP_TP") (pintype "input"))
      (node (ref "U$1") (pin "C6") (pinfunction "PDR_ON_C6") (pintype "bidirectional"))
    )
    (net (code "69") (name "Net-(U$1-PE0)") (class "Default")
      (node (ref "TP80") (pin "TP") (pinfunction "TP_TP") (pintype "input"))
      (node (ref "U$1") (pin "A4") (pinfunction "PE0_A4") (pintype "bidirectional"))
    )
    (net (code "70") (name "Net-(U$1-PE1)") (class "Default")
      (node (ref "TP79") (pin "TP") (pinfunction "TP_TP") (pintype "input"))
      (node (ref "U$1") (pin "A3") (pinfunction "PE1_A3") (pintype "bidirectional"))
    )
    (net (code "71") (name "Net-(U$1-PE2)") (class "Default")
      (node (ref "TP78") (pin "TP") (pinfunction "TP_TP") (pintype "input"))
      (node (ref "U$1") (pin "A2") (pinfunction "PE2_A2") (pintype "bidirectional"))
    )
    (net (code "72") (name "Net-(U$1-PE3)") (class "Default")
      (node (ref "TP77") (pin "TP") (pinfunction "TP_TP") (pintype "input"))
      (node (ref "U$1") (pin "A1") (pinfunction "PE3_A1") (pintype "bidirectional"))
    )
    (net (code "73") (name "Net-(U$1-PE4)") (class "Default")
      (node (ref "TP76") (pin "TP") (pinfunction "TP_TP") (pintype "input"))
      (node (ref "U$1") (pin "B1") (pinfunction "PE4_B1") (pintype "bidirectional"))
    )
    (net (code "74") (name "Net-(U$1-PE5)") (class "Default")
      (node (ref "TP75") (pin "TP") (pinfunction "TP_TP") (pintype "input"))
      (node (ref "U$1") (pin "B2") (pinfunction "PE5_B2") (pintype "bidirectional"))
    )
    (net (code "75") (name "Net-(U$1-PE6)") (class "Default")
      (node (ref "TP74") (pin "TP") (pinfunction "TP_TP") (pintype "input"))
      (node (ref "U$1") (pin "B3") (pinfunction "PE6_B3") (pintype "bidirectional"))
    )
    (net (code "76") (name "Net-(U$1-PE7)") (class "Default")
      (node (ref "TP73") (pin "TP") (pinfunction "TP_TP") (pintype "input"))
      (node (ref "U$1") (pin "R8") (pinfunction "PE7_R8") (pintype "bidirectional"))
    )
    (net (code "77") (name "Net-(U$1-PE8)") (class "Default")
      (node (ref "TP72") (pin "TP") (pinfunction "TP_TP") (pintype "input"))
      (node (ref "U$1") (pin "P8") (pinfunction "PE8_P8") (pintype "bidirectional"))
    )
    (net (code "78") (name "Net-(U$1-PE9)") (class "Default")
      (node (ref "TP71") (pin "TP") (pinfunction "TP_TP") (pintype "input"))
      (node (ref "U$1") (pin "P9") (pinfunction "PE9_P9") (pintype "bidirectional"))
    )
    (net (code "79") (name "Net-(U$1-PE10)") (class "Default")
      (node (ref "TP70") (pin "TP") (pinfunction "TP_TP") (pintype "input"))
      (node (ref "U$1") (pin "R9") (pinfunction "PE10_R9") (pintype "bidirectional"))
    )
    (net (code "80") (name "Net-(U$1-PE11)") (class "Default")
      (node (ref "TP69") (pin "TP") (pinfunction "TP_TP") (pintype "input"))
      (node (ref "U$1") (pin "P10") (pinfunction "PE11_P10") (pintype "bidirectional"))
    )
    (net (code "81") (name "Net-(U$1-PE12)") (class "Default")
      (node (ref "TP68") (pin "TP") (pinfunction "TP_TP") (pintype "input"))
      (node (ref "U$1") (pin "R10") (pinfunction "PE12_R10") (pintype "bidirectional"))
    )
    (net (code "82") (name "Net-(U$1-PE13)") (class "Default")
      (node (ref "TP67") (pin "TP") (pinfunction "TP_TP") (pintype "input"))
      (node (ref "U$1") (pin "N11") (pinfunction "PE13_N11") (pintype "bidirectional"))
    )
    (net (code "83") (name "Net-(U$1-PE14)") (class "Default")
      (node (ref "TP66") (pin "TP") (pinfunction "TP_TP") (pintype "input"))
      (node (ref "U$1") (pin "P11") (pinfunction "PE14_P11") (pintype "bidirectional"))
    )
    (net (code "84") (name "Net-(U$1-PE15)") (class "Default")
      (node (ref "TP65") (pin "TP") (pinfunction "TP_TP") (pintype "input"))
      (node (ref "U$1") (pin "R11") (pinfunction "PE15_R11") (pintype "bidirectional"))
    )
    (net (code "85") (name "Net-(U$1-PF0)") (class "Default")
      (node (ref "TP64") (pin "TP") (pinfunction "TP_TP") (pintype "input"))
      (node (ref "U$1") (pin "E2") (pinfunction "PF0_E2") (pintype "bidirectional"))
    )
    (net (code "86") (name "Net-(U$1-PF1)") (class "Default")
      (node (ref "TP63") (pin "TP") (pinfunction "TP_TP") (pintype "input"))
      (node (ref "U$1") (pin "H3") (pinfunction "PF1_H3") (pintype "bidirectional"))
    )
    (net (code "87") (name "Net-(U$1-PF2)") (class "Default")
      (node (ref "TP62") (pin "TP") (pinfunction "TP_TP") (pintype "input"))
      (node (ref "U$1") (pin "H2") (pinfunction "PF2_H2") (pintype "bidirectional"))
    )
    (net (code "88") (name "Net-(U$1-PF3)") (class "Default")
      (node (ref "TP61") (pin "TP") (pinfunction "TP_TP") (pintype "input"))
      (node (ref "U$1") (pin "J2") (pinfunction "PF3_J2") (pintype "bidirectional"))
    )
    (net (code "89") (name "Net-(U$1-PF4)") (class "Default")
      (node (ref "TP60") (pin "TP") (pinfunction "TP_TP") (pintype "input"))
      (node (ref "U$1") (pin "J3") (pinfunction "PF4_J3") (pintype "bidirectional"))
    )
    (net (code "90") (name "Net-(U$1-PF5)") (class "Default")
      (node (ref "TP59") (pin "TP") (pinfunction "TP_TP") (pintype "input"))
      (node (ref "U$1") (pin "K3") (pinfunction "PF5_K3") (pintype "bidirectional"))
    )
    (net (code "91") (name "Net-(U$1-PF6)") (class "Default")
      (node (ref "TP58") (pin "TP") (pinfunction "TP_TP") (pintype "input"))
      (node (ref "U$1") (pin "K2") (pinfunction "PF6_K2") (pintype "bidirectional"))
    )
    (net (code "92") (name "Net-(U$1-PF7)") (class "Default")
      (node (ref "TP57") (pin "TP") (pinfunction "TP_TP") (pintype "input"))
      (node (ref "U$1") (pin "K1") (pinfunction "PF7_K1") (pintype "bidirectional"))
    )
    (net (code "93") (name "Net-(U$1-PF8)") (class "Default")
      (node (ref "TP56") (pin "TP") (pinfunction "TP_TP") (pintype "input"))
      (node (ref "U$1") (pin "L3") (pinfunction "PF8_L3") (pintype "bidirectional"))
    )
    (net (code "94") (name "Net-(U$1-PF9)") (class "Default")
      (node (ref "TP55") (pin "TP") (pinfunction "TP_TP") (pintype "input"))
      (node (ref "U$1") (pin "L2") (pinfunction "PF9_L2") (pintype "bidirectional"))
    )
    (net (code "95") (name "Net-(U$1-PF10)") (class "Default")
      (node (ref "TP54") (pin "TP") (pinfunction "TP_TP") (pintype "input"))
      (node (ref "U$1") (pin "L1") (pinfunction "PF10_L1") (pintype "bidirectional"))
    )
    (net (code "96") (name "Net-(U$1-PF11)") (class "Default")
      (node (ref "TP53") (pin "TP") (pinfunction "TP_TP") (pintype "input"))
      (node (ref "U$1") (pin "R6") (pinfunction "PF11_R6") (pintype "bidirectional"))
    )
    (net (code "97") (name "Net-(U$1-PF12)") (class "Default")
      (node (ref "TP52") (pin "TP") (pinfunction "TP_TP") (pintype "input"))
      (node (ref "U$1") (pin "P6") (pinfunction "PF12_P6") (pintype "bidirectional"))
    )
    (net (code "98") (name "Net-(U$1-PF13)") (class "Default")
      (node (ref "TP51") (pin "TP") (pinfunction "TP_TP") (pintype "input"))
      (node (ref "U$1") (pin "N6") (pinfunction "PF13_N6") (pintype "bidirectional"))
    )
    (net (code "99") (name "Net-(U$1-PF14)") (class "Default")
      (node (ref "TP50") (pin "TP") (pinfunction "TP_TP") (pintype "input"))
      (node (ref "U$1") (pin "R7") (pinfunction "PF14_R7") (pintype "bidirectional"))
    )
    (net (code "100") (name "Net-(U$1-PF15)") (class "Default")
      (node (ref "TP49") (pin "TP") (pinfunction "TP_TP") (pintype "input"))
      (node (ref "U$1") (pin "P7") (pinfunction "PF15_P7") (pintype "bidirectional"))
    )
    (net (code "101") (name "Net-(U$1-PG0)") (class "Default")
      (node (ref "TP140") (pin "TP") (pinfunction "TP_TP") (pintype "input"))
      (node (ref "U$1") (pin "N7") (pinfunction "PG0_N7") (pintype "bidirectional"))
    )
    (net (code "102") (name "Net-(U$1-PG1)") (class "Default")
      (node (ref "TP139") (pin "TP") (pinfunction "TP_TP") (pintype "input"))
      (node (ref "U$1") (pin "M7") (pinfunction "PG1_M7") (pintype "bidirectional"))
    )
    (net (code "103") (name "Net-(U$1-PG2)") (class "Default")
      (node (ref "TP138") (pin "TP") (pinfunction "TP_TP") (pintype "input"))
      (node (ref "U$1") (pin "L15") (pinfunction "PG2_L15") (pintype "bidirectional"))
    )
    (net (code "104") (name "Net-(U$1-PG3)") (class "Default")
      (node (ref "TP137") (pin "TP") (pinfunction "TP_TP") (pintype "input"))
      (node (ref "U$1") (pin "K15") (pinfunction "PG3_K15") (pintype "bidirectional"))
    )
    (net (code "105") (name "Net-(U$1-PG4)") (class "Default")
      (node (ref "TP136") (pin "TP") (pinfunction "TP_TP") (pintype "input"))
      (node (ref "U$1") (pin "K14") (pinfunction "PG4_K14") (pintype "bidirectional"))
    )
    (net (code "106") (name "Net-(U$1-PG5)") (class "Default")
      (node (ref "TP135") (pin "TP") (pinfunction "TP_TP") (pintype "input"))
      (node (ref "U$1") (pin "K13") (pinfunction "PG5_K13") (pintype "bidirectional"))
    )
    (net (code "107") (name "Net-(U$1-PG6)") (class "Default")
      (node (ref "TP134") (pin "TP") (pinfunction "TP_TP") (pintype "input"))
      (node (ref "U$1") (pin "J15") (pinfunction "PG6_J15") (pintype "bidirectional"))
    )
    (net (code "108") (name "Net-(U$1-PG7)") (class "Default")
      (node (ref "TP133") (pin "TP") (pinfunction "TP_TP") (pintype "input"))
      (node (ref "U$1") (pin "J14") (pinfunction "PG7_J14") (pintype "bidirectional"))
    )
    (net (code "109") (name "Net-(U$1-PG8)") (class "Default")
      (node (ref "TP132") (pin "TP") (pinfunction "TP_TP") (pintype "input"))
      (node (ref "U$1") (pin "H14") (pinfunction "PG8_H14") (pintype "bidirectional"))
    )
    (net (code "110") (name "Net-(U$1-PG9)") (class "Default")
      (node (ref "TP131") (pin "TP") (pinfunction "TP_TP") (pintype "input"))
      (node (ref "U$1") (pin "C10") (pinfunction "PG9_C10") (pintype "bidirectional"))
    )
    (net (code "111") (name "Net-(U$1-PG10)") (class "Default")
      (node (ref "TP130") (pin "TP") (pinfunction "TP_TP") (pintype "input"))
      (node (ref "U$1") (pin "B10") (pinfunction "PG10_B10") (pintype "bidirectional"))
    )
    (net (code "112") (name "Net-(U$1-PG11)") (class "Default")
      (node (ref "TP129") (pin "TP") (pinfunction "TP_TP") (pintype "input"))
      (node (ref "U$1") (pin "B9") (pinfunction "PG11_B9") (pintype "bidirectional"))
    )
    (net (code "113") (name "Net-(U$1-PG12)") (class "Default")
      (node (ref "TP128") (pin "TP") (pinfunction "TP_TP") (pintype "input"))
      (node (ref "U$1") (pin "B8") (pinfunction "PG12_B8") (pintype "bidirectional"))
    )
    (net (code "114") (name "Net-(U$1-PG13)") (class "Default")
      (node (ref "TP127") (pin "TP") (pinfunction "TP_TP") (pintype "input"))
      (node (ref "U$1") (pin "A8") (pinfunction "PG13_A8") (pintype "bidirectional"))
    )
    (net (code "115") (name "Net-(U$1-PG14)") (class "Default")
      (node (ref "TP126") (pin "TP") (pinfunction "TP_TP") (pintype "input"))
      (node (ref "U$1") (pin "A7") (pinfunction "PG14_A7") (pintype "bidirectional"))
    )
    (net (code "116") (name "Net-(U$1-PG15)") (class "Default")
      (node (ref "TP125") (pin "TP") (pinfunction "TP_TP") (pintype "input"))
      (node (ref "U$1") (pin "B7") (pinfunction "PG15_B7") (pintype "bidirectional"))
    )
    (net (code "117") (name "Net-(U$1-PH0)") (class "Default")
      (node (ref "TP124") (pin "TP") (pinfunction "TP_TP") (pintype "input"))
      (node (ref "U$1") (pin "G1") (pinfunction "PH0_G1") (pintype "bidirectional"))
    )
    (net (code "118") (name "Net-(U$1-PH1)") (class "Default")
      (node (ref "TP123") (pin "TP") (pinfunction "TP_TP") (pintype "input"))
      (node (ref "U$1") (pin "H1") (pinfunction "PH1_H1") (pintype "bidirectional"))
    )
    (net (code "119") (name "Net-(U$1-PH2)") (class "Default")
      (node (ref "TP122") (pin "TP") (pinfunction "TP_TP") (pintype "input"))
      (node (ref "U$1") (pin "F4") (pinfunction "PH2_F4") (pintype "bidirectional"))
    )
    (net (code "120") (name "Net-(U$1-PH3)") (class "Default")
      (node (ref "TP121") (pin "TP") (pinfunction "TP_TP") (pintype "input"))
      (node (ref "U$1") (pin "G4") (pinfunction "PH3_G4") (pintype "bidirectional"))
    )
    (net (code "121") (name "Net-(U$1-PH4)") (class "Default")
      (node (ref "TP120") (pin "TP") (pinfunction "TP_TP") (pintype "input"))
      (node (ref "U$1") (pin "H4") (pinfunction "PH4_H4") (pintype "bidirectional"))
    )
    (net (code "122") (name "Net-(U$1-PH5)") (class "Default")
      (node (ref "TP119") (pin "TP") (pinfunction "TP_TP") (pintype "input"))
      (node (ref "U$1") (pin "J4") (pinfunction "PH5_J4") (pintype "bidirectional"))
    )
    (net (code "123") (name "Net-(U$1-PH6)") (class "Default")
      (node (ref "TP118") (pin "TP") (pinfunction "TP_TP") (pintype "input"))
      (node (ref "U$1") (pin "M11") (pinfunction "PH6_M11") (pintype "bidirectional"))
    )
    (net (code "124") (name "Net-(U$1-PH7)") (class "Default")
      (node (ref "TP117") (pin "TP") (pinfunction "TP_TP") (pintype "input"))
      (node (ref "U$1") (pin "N12") (pinfunction "PH7_N12") (pintype "bidirectional"))
    )
    (net (code "125") (name "Net-(U$1-PH8)") (class "Default")
      (node (ref "TP116") (pin "TP") (pinfunction "TP_TP") (pintype "input"))
      (node (ref "U$1") (pin "M12") (pinfunction "PH8_M12") (pintype "bidirectional"))
    )
    (net (code "126") (name "Net-(U$1-PH9)") (class "Default")
      (node (ref "TP115") (pin "TP") (pinfunction "TP_TP") (pintype "input"))
      (node (ref "U$1") (pin "M13") (pinfunction "PH9_M13") (pintype "bidirectional"))
    )
    (net (code "127") (name "Net-(U$1-PH10)") (class "Default")
      (node (ref "TP114") (pin "TP") (pinfunction "TP_TP") (pintype "input"))
      (node (ref "U$1") (pin "L13") (pinfunction "PH10_L13") (pintype "bidirectional"))
    )
    (net (code "128") (name "Net-(U$1-PH11)") (class "Default")
      (node (ref "TP113") (pin "TP") (pinfunction "TP_TP") (pintype "input"))
      (node (ref "U$1") (pin "L12") (pinfunction "PH11_L12") (pintype "bidirectional"))
    )
    (net (code "129") (name "Net-(U$1-PH12)") (class "Default")
      (node (ref "TP112") (pin "TP") (pinfunction "TP_TP") (pintype "input"))
      (node (ref "U$1") (pin "K12") (pinfunction "PH12_K12") (pintype "bidirectional"))
    )
    (net (code "130") (name "Net-(U$1-PH13)") (class "Default")
      (node (ref "TP111") (pin "TP") (pinfunction "TP_TP") (pintype "input"))
      (node (ref "U$1") (pin "E12") (pinfunction "PH13_E12") (pintype "bidirectional"))
    )
    (net (code "131") (name "Net-(U$1-PH14)") (class "Default")
      (node (ref "TP110") (pin "TP") (pinfunction "TP_TP") (pintype "input"))
      (node (ref "U$1") (pin "E13") (pinfunction "PH14_E13") (pintype "bidirectional"))
    )
    (net (code "132") (name "Net-(U$1-PH15)") (class "Default")
      (node (ref "TP109") (pin "TP") (pinfunction "TP_TP") (pintype "input"))
      (node (ref "U$1") (pin "D13") (pinfunction "PH15_D13") (pintype "bidirectional"))
    )
    (net (code "133") (name "Net-(U$1-PI0)") (class "Default")
      (node (ref "TP108") (pin "TP") (pinfunction "TP_TP") (pintype "input"))
      (node (ref "U$1") (pin "E14") (pinfunction "PI0_E14") (pintype "bidirectional"))
    )
    (net (code "134") (name "Net-(U$1-PI1)") (class "Default")
      (node (ref "TP107") (pin "TP") (pinfunction "TP_TP") (pintype "input"))
      (node (ref "U$1") (pin "D14") (pinfunction "PI1_D14") (pintype "bidirectional"))
    )
    (net (code "135") (name "Net-(U$1-PI2)") (class "Default")
      (node (ref "TP106") (pin "TP") (pinfunction "TP_TP") (pintype "input"))
      (node (ref "U$1") (pin "C14") (pinfunction "PI2_C14") (pintype "bidirectional"))
    )
    (net (code "136") (name "Net-(U$1-PI3)") (class "Default")
      (node (ref "TP105") (pin "TP") (pinfunction "TP_TP") (pintype "input"))
      (node (ref "U$1") (pin "C13") (pinfunction "PI3_C13") (pintype "bidirectional"))
    )
    (net (code "137") (name "Net-(U$1-PI4)") (class "Default")
      (node (ref "TP104") (pin "TP") (pinfunction "TP_TP") (pintype "input"))
      (node (ref "U$1") (pin "D4") (pinfunction "PI4_D4") (pintype "bidirectional"))
    )
    (net (code "138") (name "Net-(U$1-PI5)") (class "Default")
      (node (ref "TP103") (pin "TP") (pinfunction "TP_TP") (pintype "input"))
      (node (ref "U$1") (pin "C4") (pinfunction "PI5_C4") (pintype "bidirectional"))
    )
    (net (code "139") (name "Net-(U$1-PI6)") (class "Default")
      (node (ref "TP102") (pin "TP") (pinfunction "TP_TP") (pintype "input"))
      (node (ref "U$1") (pin "C3") (pinfunction "PI6_C3") (pintype "bidirectional"))
    )
    (net (code "140") (name "Net-(U$1-PI7)") (class "Default")
      (node (ref "TP101") (pin "TP") (pinfunction "TP_TP") (pintype "input"))
      (node (ref "U$1") (pin "C2") (pinfunction "PI7_C2") (pintype "bidirectional"))
    )
    (net (code "141") (name "Net-(U$1-PI8)") (class "Default")
      (node (ref "TP100") (pin "TP") (pinfunction "TP_TP") (pintype "input"))
      (node (ref "U$1") (pin "D2") (pinfunction "PI8_D2") (pintype "bidirectional"))
    )
    (net (code "142") (name "Net-(U$1-PI9)") (class "Default")
      (node (ref "TP99") (pin "TP") (pinfunction "TP_TP") (pintype "input"))
      (node (ref "U$1") (pin "D3") (pinfunction "PI9_D3") (pintype "bidirectional"))
    )
    (net (code "143") (name "Net-(U$1-PI10)") (class "Default")
      (node (ref "TP98") (pin "TP") (pinfunction "TP_TP") (pintype "input"))
      (node (ref "U$1") (pin "E3") (pinfunction "PI10_E3") (pintype "bidirectional"))
    )
    (net (code "144") (name "Net-(U$1-PI11)") (class "Default")
      (node (ref "TP97") (pin "TP") (pinfunction "TP_TP") (pintype "input"))
      (node (ref "U$1") (pin "E4") (pinfunction "PI11_E4") (pintype "bidirectional"))
    )
    (net (code "145") (name "Net-(U$1-VCAP_1)") (class "Default")
      (node (ref "TP200") (pin "TP") (pinfunction "TP_TP") (pintype "input"))
      (node (ref "U$1") (pin "M10") (pinfunction "VCAP_1_M10") (pintype "bidirectional"))
    )
    (net (code "146") (name "Net-(U$1-VCAP_2)") (class "Default")
      (node (ref "TP199") (pin "TP") (pinfunction "TP_TP") (pintype "input"))
      (node (ref "U$1") (pin "F13") (pinfunction "VCAP_2_F13") (pintype "bidirectional"))
    )
    (net (code "147") (name "Net-(U$1-VREF+)") (class "Default")
      (node (ref "TP195") (pin "TP") (pinfunction "TP_TP") (pintype "input"))
      (node (ref "U$1") (pin "P1") (pinfunction "VREF+_P1") (pintype "bidirectional"))
    )
    (net (code "148") (name "Net-(U$1-VREF-)") (class "Default")
      (node (ref "TP196") (pin "TP") (pinfunction "TP_TP") (pintype "input"))
      (node (ref "U$1") (pin "N1") (pinfunction "VREF-_N1") (pintype "bidirectional"))
    )
    (net (code "149") (name "unconnected-(U$1-GND-PadD5)") (class "Default")
      (node (ref "U$1") (pin "D5") (pinfunction "GND_D5") (pintype "bidirectional"))
    )
    (net (code "150") (name "unconnected-(U$1-GND-PadD7)") (class "Default")
      (node (ref "U$1") (pin "D7") (pinfunction "GND_D7") (pintype "bidirectional"))
    )
    (net (code "151") (name "unconnected-(U$1-GND-PadD8)") (class "Default")
      (node (ref "U$1") (pin "D8") (pinfunction "GND_D8") (pintype "bidirectional"))
    )
    (net (code "152") (name "unconnected-(U$1-GND-PadD9)") (class "Default")
      (node (ref "U$1") (pin "D9") (pinfunction "GND_D9") (pintype "bidirectional"))
    )
    (net (code "153") (name "unconnected-(U$1-GND-PadF2)") (class "Default")
      (node (ref "U$1") (pin "F2") (pinfunction "GND_F2") (pintype "bidirectional"))
    )
    (net (code "154") (name "unconnected-(U$1-GND-PadF6)") (class "Default")
      (node (ref "U$1") (pin "F6") (pinfunction "GND_F6") (pintype "bidirectional"))
    )
    (net (code "155") (name "unconnected-(U$1-GND-PadF7)") (class "Default")
      (node (ref "U$1") (pin "F7") (pinfunction "GND_F7") (pintype "bidirectional"))
    )
    (net (code "156") (name "unconnected-(U$1-GND-PadF8)") (class "Default")
      (node (ref "U$1") (pin "F8") (pinfunction "GND_F8") (pintype "bidirectional"))
    )
    (net (code "157") (name "unconnected-(U$1-GND-PadF9)") (class "Default")
      (node (ref "U$1") (pin "F9") (pinfunction "GND_F9") (pintype "bidirectional"))
    )
    (net (code "158") (name "unconnected-(U$1-GND-PadF10)") (class "Default")
      (node (ref "U$1") (pin "F10") (pinfunction "GND_F10") (pintype "bidirectional"))
    )
    (net (code "159") (name "unconnected-(U$1-GND-PadF12)") (class "Default")
      (node (ref "U$1") (pin "F12") (pinfunction "GND_F12") (pintype "bidirectional"))
    )
    (net (code "160") (name "unconnected-(U$1-GND-PadG2)") (class "Default")
      (node (ref "U$1") (pin "G2") (pinfunction "GND_G2") (pintype "bidirectional"))
    )
    (net (code "161") (name "unconnected-(U$1-GND-PadG6)") (class "Default")
      (node (ref "U$1") (pin "G6") (pinfunction "GND_G6") (pintype "bidirectional"))
    )
    (net (code "162") (name "unconnected-(U$1-GND-PadG7)") (class "Default")
      (node (ref "U$1") (pin "G7") (pinfunction "GND_G7") (pintype "bidirectional"))
    )
    (net (code "163") (name "unconnected-(U$1-GND-PadG8)") (class "Default")
      (node (ref "U$1") (pin "G8") (pinfunction "GND_G8") (pintype "bidirectional"))
    )
    (net (code "164") (name "unconnected-(U$1-GND-PadG9)") (class "Default")
      (node (ref "U$1") (pin "G9") (pinfunction "GND_G9") (pintype "bidirectional"))
    )
    (net (code "165") (name "unconnected-(U$1-GND-PadG10)") (class "Default")
      (node (ref "U$1") (pin "G10") (pinfunction "GND_G10") (pintype "bidirectional"))
    )
    (net (code "166") (name "unconnected-(U$1-GND-PadG12)") (class "Default")
      (node (ref "U$1") (pin "G12") (pinfunction "GND_G12") (pintype "bidirectional"))
    )
    (net (code "167") (name "unconnected-(U$1-GND-PadH6)") (class "Default")
      (node (ref "U$1") (pin "H6") (pinfunction "GND_H6") (pintype "bidirectional"))
    )
    (net (code "168") (name "unconnected-(U$1-GND-PadH7)") (class "Default")
      (node (ref "U$1") (pin "H7") (pinfunction "GND_H7") (pintype "bidirectional"))
    )
    (net (code "169") (name "unconnected-(U$1-GND-PadH8)") (class "Default")
      (node (ref "U$1") (pin "H8") (pinfunction "GND_H8") (pintype "bidirectional"))
    )
    (net (code "170") (name "unconnected-(U$1-GND-PadH9)") (class "Default")
      (node (ref "U$1") (pin "H9") (pinfunction "GND_H9") (pintype "bidirectional"))
    )
    (net (code "171") (name "unconnected-(U$1-GND-PadH10)") (class "Default")
      (node (ref "U$1") (pin "H10") (pinfunction "GND_H10") (pintype "bidirectional"))
    )
    (net (code "172") (name "unconnected-(U$1-GND-PadH12)") (class "Default")
      (node (ref "U$1") (pin "H12") (pinfunction "GND_H12") (pintype "bidirectional"))
    )
    (net (code "173") (name "unconnected-(U$1-GND-PadJ6)") (class "Default")
      (node (ref "U$1") (pin "J6") (pinfunction "GND_J6") (pintype "bidirectional"))
    )
    (net (code "174") (name "unconnected-(U$1-GND-PadJ7)") (class "Default")
      (node (ref "U$1") (pin "J7") (pinfunction "GND_J7") (pintype "bidirectional"))
    )
    (net (code "175") (name "unconnected-(U$1-GND-PadJ8)") (class "Default")
      (node (ref "U$1") (pin "J8") (pinfunction "GND_J8") (pintype "bidirectional"))
    )
    (net (code "176") (name "unconnected-(U$1-GND-PadJ9)") (class "Default")
      (node (ref "U$1") (pin "J9") (pinfunction "GND_J9") (pintype "bidirectional"))
    )
    (net (code "177") (name "unconnected-(U$1-GND-PadJ10)") (class "Default")
      (node (ref "U$1") (pin "J10") (pinfunction "GND_J10") (pintype "bidirectional"))
    )
    (net (code "178") (name "unconnected-(U$1-GND-PadK6)") (class "Default")
      (node (ref "U$1") (pin "K6") (pinfunction "GND_K6") (pintype "bidirectional"))
    )
    (net (code "179") (name "unconnected-(U$1-GND-PadK7)") (class "Default")
      (node (ref "U$1") (pin "K7") (pinfunction "GND_K7") (pintype "bidirectional"))
    )
    (net (code "180") (name "unconnected-(U$1-GND-PadK8)") (class "Default")
      (node (ref "U$1") (pin "K8") (pinfunction "GND_K8") (pintype "bidirectional"))
    )
    (net (code "181") (name "unconnected-(U$1-GND-PadK9)") (class "Default")
      (node (ref "U$1") (pin "K9") (pinfunction "GND_K9") (pintype "bidirectional"))
    )
    (net (code "182") (name "unconnected-(U$1-GND-PadK10)") (class "Default")
      (node (ref "U$1") (pin "K10") (pinfunction "GND_K10") (pintype "bidirectional"))
    )
    (net (code "183") (name "unconnected-(U$1-GND-PadM8)") (class "Default")
      (node (ref "U$1") (pin "M8") (pinfunction "GND_M8") (pintype "bidirectional"))
    )
    (net (code "184") (name "unconnected-(U$1-GND-PadM9)") (class "Default")
      (node (ref "U$1") (pin "M9") (pinfunction "GND_M9") (pintype "bidirectional"))
    )
    (net (code "185") (name "unconnected-(U$1-VBAT-PadC1)") (class "Default")
      (node (ref "U$1") (pin "C1") (pinfunction "VBAT_C1") (pintype "bidirectional"))
    )
    (net (code "186") (name "unconnected-(U$1-VDD-PadC5)") (class "Default")
      (node (ref "U$1") (pin "C5") (pinfunction "VDD_C5") (pintype "bidirectional"))
    )
    (net (code "187") (name "unconnected-(U$1-VDD-PadC7)") (class "Default")
      (node (ref "U$1") (pin "C7") (pinfunction "VDD_C7") (pintype "bidirectional"))
    )
    (net (code "188") (name "unconnected-(U$1-VDD-PadC8)") (class "Default")
      (node (ref "U$1") (pin "C8") (pinfunction "VDD_C8") (pintype "bidirectional"))
    )
    (net (code "189") (name "unconnected-(U$1-VDD-PadC9)") (class "Default")
      (node (ref "U$1") (pin "C9") (pinfunction "VDD_C9") (pintype "bidirectional"))
    )
    (net (code "190") (name "unconnected-(U$1-VDD-PadF3)") (class "Default")
      (node (ref "U$1") (pin "F3") (pinfunction "VDD_F3") (pintype "bidirectional"))
    )
    (net (code "191") (name "unconnected-(U$1-VDD-PadG3)") (class "Default")
      (node (ref "U$1") (pin "G3") (pinfunction "VDD_G3") (pintype "bidirectional"))
    )
    (net (code "192") (name "unconnected-(U$1-VDD-PadG13)") (class "Default")
      (node (ref "U$1") (pin "G13") (pinfunction "VDD_G13") (pintype "bidirectional"))
    )
    (net (code "193") (name "unconnected-(U$1-VDD-PadH13)") (class "Default")
      (node (ref "U$1") (pin "H13") (pinfunction "VDD_H13") (pintype "bidirectional"))
    )
    (net (code "194") (name "unconnected-(U$1-VDD-PadJ12)") (class "Default")
      (node (ref "U$1") (pin "J12") (pinfunction "VDD_J12") (pintype "bidirectional"))
    )
    (net (code "195") (name "unconnected-(U$1-VDD-PadJ13)") (class "Default")
      (node (ref "U$1") (pin "J13") (pinfunction "VDD_J13") (pintype "bidirectional"))
    )
    (net (code "196") (name "unconnected-(U$1-VDD-PadK4)") (class "Default")
      (node (ref "U$1") (pin "K4") (pinfunction "VDD_K4") (pintype "bidirectional"))
    )
    (net (code "197") (name "unconnected-(U$1-VDD-PadN8)") (class "Default")
      (node (ref "U$1") (pin "N8") (pinfunction "VDD_N8") (pintype "bidirectional"))
    )
    (net (code "198") (name "unconnected-(U$1-VDD-PadN9)") (class "Default")
      (node (ref "U$1") (pin "N9") (pinfunction "VDD_N9") (pintype "bidirectional"))
    )
    (net (code "199") (name "unconnected-(U$1-VDD-PadN10)") (class "Default")
      (node (ref "U$1") (pin "N10") (pinfunction "VDD_N10") (pintype "bidirectional"))
    )
    (net (code "200") (name "unconnected-(U$1-VDDA-PadR1)") (class "Default")
      (node (ref "U$1") (pin "R1") (pinfunction "VDDA_R1") (pintype "bidirectional"))
    )
    (net (code "201") (name "unconnected-(U$1-VSSA-PadM1)") (class "Default")
      (node (ref "U$1") (pin "M1") (pinfunction "VSSA_M1") (pintype "bidirectional"))
    )
  )
)
